# Sensor_PCB_M1.net
KiCad netlist of a schematic drawn in EAGLE
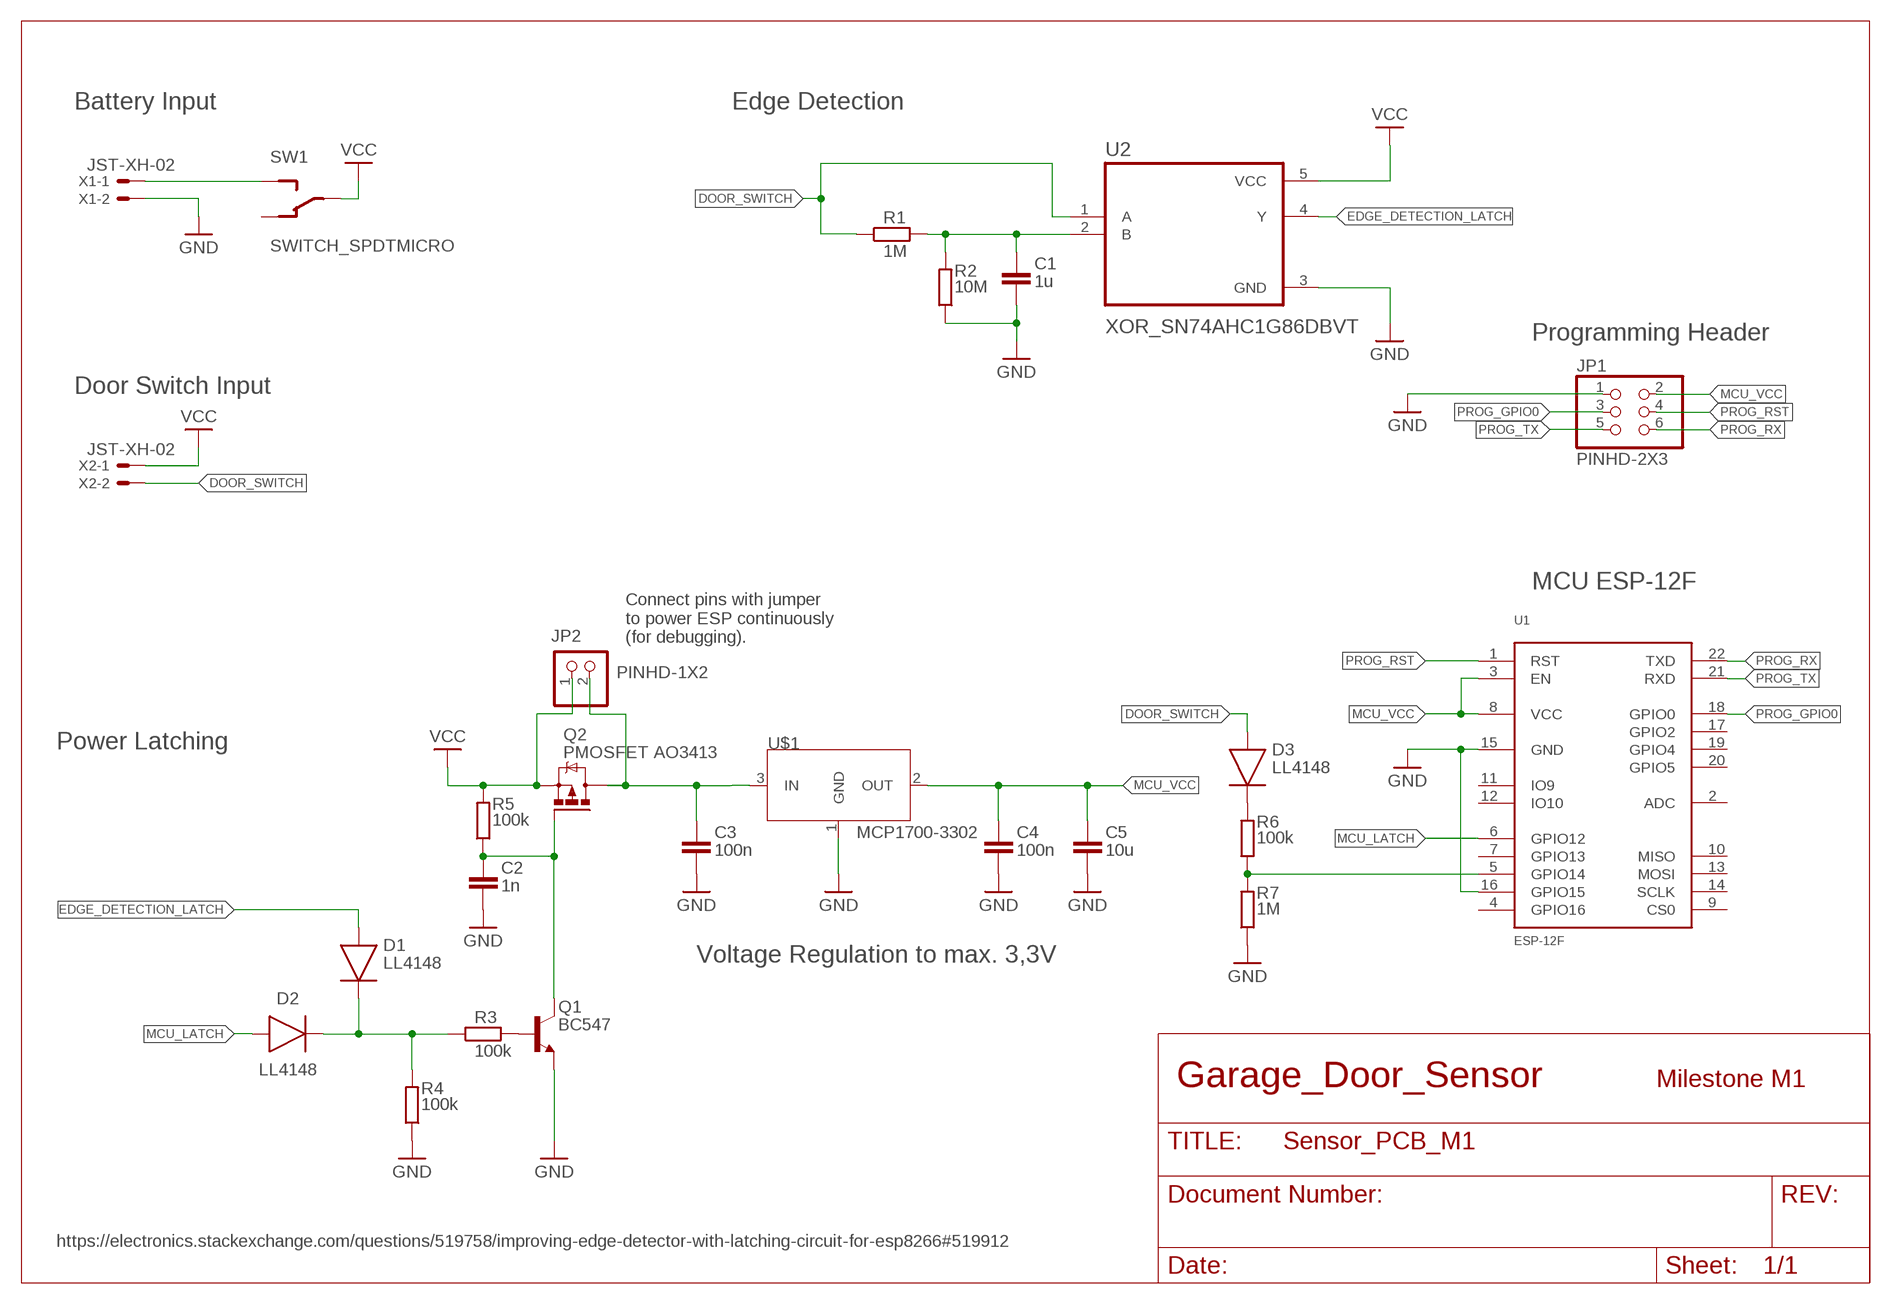
[diagram p0: schematic, sheet 1]

(export (version "E")
  (design (tool "Eeschema 10.0.6"))
  (components
    (comp (ref "C1")
      (value "1u")
      (footprint "eagle-import:CAPC2012X110")
      (libsource (lib "eagle-import") (part "CCHIP-0805(2012-METRIC)_"))
    )
    (comp (ref "C2")
      (value "1n")
      (footprint "eagle-import:CAPC2012X110")
      (libsource (lib "eagle-import") (part "CCHIP-0805(2012-METRIC)_"))
    )
    (comp (ref "C3")
      (value "100n")
      (footprint "eagle-import:CAPC2012X110")
      (libsource (lib "eagle-import") (part "CCHIP-0805(2012-METRIC)_"))
    )
    (comp (ref "C4")
      (value "100n")
      (footprint "eagle-import:CAPC2012X110")
      (libsource (lib "eagle-import") (part "CCHIP-0805(2012-METRIC)_"))
    )
    (comp (ref "C5")
      (value "10u")
      (footprint "eagle-import:CAPC2012X110")
      (libsource (lib "eagle-import") (part "CCHIP-0805(2012-METRIC)_"))
    )
    (comp (ref "D1")
      (value "LL4148")
      (footprint "eagle-import:DIOMELF3516")
      (fields (field (name "MANUFACTURER") "ON Semiconductor "))
      (libsource (lib "eagle-import") (part "DIODE__SOD-80LL4148"))
    )
    (comp (ref "D2")
      (value "LL4148")
      (footprint "eagle-import:DIOMELF3516")
      (fields (field (name "MANUFACTURER") "ON Semiconductor "))
      (libsource (lib "eagle-import") (part "DIODE__SOD-80LL4148"))
    )
    (comp (ref "D3")
      (value "LL4148")
      (footprint "eagle-import:DIOMELF3516")
      (fields (field (name "MANUFACTURER") "ON Semiconductor "))
      (libsource (lib "eagle-import") (part "DIODE__SOD-80LL4148"))
    )
    (comp (ref "JP1")
      (value "PINHD-2X3")
      (footprint "eagle-import:2X03")
      (fields (field (name "MANUFACTURER") "Generic"))
      (libsource (lib "eagle-import") (part "PINHD-2X3"))
    )
    (comp (ref "JP2")
      (value "PINHD-1X2")
      (footprint "eagle-import:1X02")
      (fields (field (name "MANUFACTURER") "Generic"))
      (libsource (lib "eagle-import") (part "PINHD-1X2"))
    )
    (comp (ref "Q1")
      (value "BC547")
      (footprint "eagle-import:SOT95P237X112-3N")
      (libsource (lib "eagle-import") (part "NPNSOT23-BEC_"))
    )
    (comp (ref "Q2")
      (value "PMOSFET AO3413")
      (footprint "eagle-import:SOT23")
      (libsource (lib "eagle-import") (part "PMOSFETSOT23-GSD_"))
    )
    (comp (ref "R1")
      (value "1M")
      (footprint "eagle-import:R0805")
      (libsource (lib "eagle-import") (part "R-EU_R0805"))
    )
    (comp (ref "R2")
      (value "10M")
      (footprint "eagle-import:R0805")
      (libsource (lib "eagle-import") (part "R-EU_R0805"))
    )
    (comp (ref "R3")
      (value "100k")
      (footprint "eagle-import:R0805")
      (libsource (lib "eagle-import") (part "R-EU_R0805"))
    )
    (comp (ref "R4")
      (value "100k")
      (footprint "eagle-import:R0805")
      (libsource (lib "eagle-import") (part "R-EU_R0805"))
    )
    (comp (ref "R5")
      (value "100k")
      (footprint "eagle-import:R0805")
      (libsource (lib "eagle-import") (part "R-EU_R0805"))
    )
    (comp (ref "R6")
      (value "100k")
      (footprint "eagle-import:R0805")
      (libsource (lib "eagle-import") (part "R-EU_R0805"))
    )
    (comp (ref "R7")
      (value "1M")
      (footprint "eagle-import:R0805")
      (libsource (lib "eagle-import") (part "R-EU_R0805"))
    )
    (comp (ref "SW1")
      (value "SWITCH_SPDTMICRO")
      (footprint "eagle-import:MICROSWITCH_SPDT")
      (libsource (lib "eagle-import") (part "SWITCH_SPDTMICRO"))
    )
    (comp (ref "U$1")
      (value "MCP1700-3302")
      (footprint "eagle-import:SOT23")
      (libsource (lib "eagle-import") (part "MCP1700-3302"))
    )
    (comp (ref "U1")
      (value "ESP-12F")
      (footprint "eagle-import:ESP-12F")
      (fields (field (name "MF") "AI-Thinker"))
      (libsource (lib "eagle-import") (part "ESP-12F"))
    )
    (comp (ref "U2")
      (value "XOR_SN74AHC1G86DBVT")
      (footprint "eagle-import:SOT95P280X145-5N")
      (fields (field (name "MF") "Texas Instruments") (field (name "MP") "SN74AHC1G86DBVT"))
      (libsource (lib "eagle-import") (part "SN74AHC1G86DBVT"))
    )
    (comp (ref "X1")
      (value "JST-XH-02")
      (footprint "eagle-import:JST-XH-02-PACKAGE-LONG-PAD")
      (libsource (lib "eagle-import") (part "JST-XH-02-PIN-LONG-PAD"))
    )
    (comp (ref "X2")
      (value "JST-XH-02")
      (footprint "eagle-import:JST-XH-02-PACKAGE-LONG-PAD")
      (libsource (lib "eagle-import") (part "JST-XH-02-PIN-LONG-PAD"))
    )
  )
  (nets
    (net (code "1") (name "DOOR_SWITCH") (class "Default")
      (node (ref "D3") (pin "2") (pinfunction "A_2") (pintype "passive"))
      (node (ref "R1") (pin "1") (pinfunction "1_1") (pintype "passive"))
      (node (ref "U2") (pin "1") (pinfunction "A_1") (pintype "input"))
      (node (ref "X2") (pin "2") (pinfunction "S_2") (pintype "passive"))
    )
    (net (code "2") (name "EDGE_DETECTION_LATCH") (class "Default")
      (node (ref "D1") (pin "2") (pinfunction "A_2") (pintype "passive"))
      (node (ref "U2") (pin "4") (pinfunction "Y_4") (pintype "output"))
    )
    (net (code "3") (name "GND") (class "Default")
      (node (ref "C1") (pin "2") (pinfunction "2_2") (pintype "passive"))
      (node (ref "C2") (pin "2") (pinfunction "2_2") (pintype "passive"))
      (node (ref "C3") (pin "2") (pinfunction "2_2") (pintype "passive"))
      (node (ref "C4") (pin "2") (pinfunction "2_2") (pintype "passive"))
      (node (ref "C5") (pin "2") (pinfunction "2_2") (pintype "passive"))
      (node (ref "JP1") (pin "1") (pinfunction "1_1") (pintype "passive"))
      (node (ref "Q1") (pin "2") (pinfunction "E_2") (pintype "passive"))
      (node (ref "R2") (pin "1") (pinfunction "1_1") (pintype "passive"))
      (node (ref "R4") (pin "1") (pinfunction "1_1") (pintype "passive"))
      (node (ref "R7") (pin "1") (pinfunction "1_1") (pintype "passive"))
      (node (ref "U$1") (pin "1") (pinfunction "GND_1") (pintype "bidirectional"))
      (node (ref "U1") (pin "15") (pinfunction "GND_15") (pintype "bidirectional"))
      (node (ref "U1") (pin "16") (pinfunction "GPIO15_16") (pintype "bidirectional"))
      (node (ref "U2") (pin "3") (pinfunction "GND_3") (pintype "power_in"))
      (node (ref "X1") (pin "2") (pinfunction "S_2") (pintype "passive"))
    )
    (net (code "4") (name "MCU_LATCH") (class "Default")
      (node (ref "D2") (pin "2") (pinfunction "A_2") (pintype "passive"))
      (node (ref "U1") (pin "6") (pinfunction "GPIO12_6") (pintype "bidirectional"))
    )
    (net (code "5") (name "MCU_VCC") (class "Default")
      (node (ref "C4") (pin "1") (pinfunction "1_1") (pintype "passive"))
      (node (ref "C5") (pin "1") (pinfunction "1_1") (pintype "passive"))
      (node (ref "JP1") (pin "2") (pinfunction "2_2") (pintype "passive"))
      (node (ref "U$1") (pin "2") (pinfunction "OUT_2") (pintype "bidirectional"))
      (node (ref "U1") (pin "3") (pinfunction "EN_3") (pintype "bidirectional"))
      (node (ref "U1") (pin "8") (pinfunction "VCC_8") (pintype "bidirectional"))
    )
    (net (code "6") (name "Net-(D1-C)") (class "Default")
      (node (ref "D1") (pin "1") (pinfunction "C_1") (pintype "passive"))
      (node (ref "D2") (pin "1") (pinfunction "C_1") (pintype "passive"))
      (node (ref "R3") (pin "1") (pinfunction "1_1") (pintype "passive"))
      (node (ref "R4") (pin "2") (pinfunction "2_2") (pintype "passive"))
    )
    (net (code "7") (name "Net-(D3-C)") (class "Default")
      (node (ref "D3") (pin "1") (pinfunction "C_1") (pintype "passive"))
      (node (ref "R6") (pin "2") (pinfunction "2_2") (pintype "passive"))
    )
    (net (code "8") (name "Net-(Q1-B)") (class "Default")
      (node (ref "Q1") (pin "1") (pinfunction "B_1") (pintype "passive"))
      (node (ref "R3") (pin "2") (pinfunction "2_2") (pintype "passive"))
    )
    (net (code "9") (name "Net-(Q1-C)") (class "Default")
      (node (ref "C2") (pin "1") (pinfunction "1_1") (pintype "passive"))
      (node (ref "Q1") (pin "3") (pinfunction "C_3") (pintype "passive"))
      (node (ref "Q2") (pin "1") (pinfunction "G_1") (pintype "passive"))
      (node (ref "R5") (pin "1") (pinfunction "1_1") (pintype "passive"))
    )
    (net (code "10") (name "Net-(Q2-D)") (class "Default")
      (node (ref "C3") (pin "1") (pinfunction "1_1") (pintype "passive"))
      (node (ref "JP2") (pin "2") (pinfunction "2_2") (pintype "passive"))
      (node (ref "Q2") (pin "3") (pinfunction "D_3") (pintype "passive"))
      (node (ref "U$1") (pin "3") (pinfunction "IN_3") (pintype "bidirectional"))
    )
    (net (code "11") (name "Net-(U1-GPIO14)") (class "Default")
      (node (ref "R6") (pin "1") (pinfunction "1_1") (pintype "passive"))
      (node (ref "R7") (pin "2") (pinfunction "2_2") (pintype "passive"))
      (node (ref "U1") (pin "5") (pinfunction "GPIO14_5") (pintype "bidirectional"))
    )
    (net (code "12") (name "Net-(U2-B)") (class "Default")
      (node (ref "C1") (pin "1") (pinfunction "1_1") (pintype "passive"))
      (node (ref "R1") (pin "2") (pinfunction "2_2") (pintype "passive"))
      (node (ref "R2") (pin "2") (pinfunction "2_2") (pintype "passive"))
      (node (ref "U2") (pin "2") (pinfunction "B_2") (pintype "input"))
    )
    (net (code "13") (name "Net-(X1A-S)") (class "Default")
      (node (ref "SW1") (pin "P$1") (pinfunction "P$1_P$1") (pintype "passive"))
      (node (ref "X1") (pin "1") (pinfunction "S_1") (pintype "passive"))
    )
    (net (code "14") (name "PROG_GPIO0") (class "Default")
      (node (ref "JP1") (pin "3") (pinfunction "3_3") (pintype "passive"))
      (node (ref "U1") (pin "18") (pinfunction "GPIO0_18") (pintype "bidirectional"))
    )
    (net (code "15") (name "PROG_RST") (class "Default")
      (node (ref "JP1") (pin "4") (pinfunction "4_4") (pintype "passive"))
      (node (ref "U1") (pin "1") (pinfunction "RST_1") (pintype "bidirectional"))
    )
    (net (code "16") (name "PROG_RX") (class "Default")
      (node (ref "JP1") (pin "6") (pinfunction "6_6") (pintype "passive"))
      (node (ref "U1") (pin "22") (pinfunction "TXD_22") (pintype "bidirectional"))
    )
    (net (code "17") (name "PROG_TX") (class "Default")
      (node (ref "JP1") (pin "5") (pinfunction "5_5") (pintype "passive"))
      (node (ref "U1") (pin "21") (pinfunction "RXD_21") (pintype "bidirectional"))
    )
    (net (code "18") (name "VCC") (class "Default")
      (node (ref "JP2") (pin "1") (pinfunction "1_1") (pintype "passive"))
      (node (ref "Q2") (pin "2") (pinfunction "S_2") (pintype "passive"))
      (node (ref "R5") (pin "2") (pinfunction "2_2") (pintype "passive"))
      (node (ref "SW1") (pin "P$2") (pinfunction "P$2_P$2") (pintype "passive"))
      (node (ref "U2") (pin "5") (pinfunction "VCC_5") (pintype "power_in"))
      (node (ref "X2") (pin "1") (pinfunction "S_1") (pintype "passive"))
    )
    (net (code "19") (name "unconnected-(SW1-PadP$3)") (class "Default")
      (node (ref "SW1") (pin "P$3") (pinfunction "P$3_P$3") (pintype "passive"))
    )
    (net (code "20") (name "unconnected-(U1-ADC-Pad2)") (class "Default")
      (node (ref "U1") (pin "2") (pinfunction "ADC_2") (pintype "bidirectional"))
    )
    (net (code "21") (name "unconnected-(U1-CS0-Pad9)") (class "Default")
      (node (ref "U1") (pin "9") (pinfunction "CS0_9") (pintype "bidirectional"))
    )
    (net (code "22") (name "unconnected-(U1-GPIO2-Pad17)") (class "Default")
      (node (ref "U1") (pin "17") (pinfunction "GPIO2_17") (pintype "bidirectional"))
    )
    (net (code "23") (name "unconnected-(U1-GPIO4-Pad19)") (class "Default")
      (node (ref "U1") (pin "19") (pinfunction "GPIO4_19") (pintype "bidirectional"))
    )
    (net (code "24") (name "unconnected-(U1-GPIO5-Pad20)") (class "Default")
      (node (ref "U1") (pin "20") (pinfunction "GPIO5_20") (pintype "bidirectional"))
    )
    (net (code "25") (name "unconnected-(U1-GPIO13-Pad7)") (class "Default")
      (node (ref "U1") (pin "7") (pinfunction "GPIO13_7") (pintype "bidirectional"))
    )
    (net (code "26") (name "unconnected-(U1-GPIO16-Pad4)") (class "Default")
      (node (ref "U1") (pin "4") (pinfunction "GPIO16_4") (pintype "bidirectional"))
    )
    (net (code "27") (name "unconnected-(U1-IO9-Pad11)") (class "Default")
      (node (ref "U1") (pin "11") (pinfunction "IO9_11") (pintype "bidirectional"))
    )
    (net (code "28") (name "unconnected-(U1-IO10-Pad12)") (class "Default")
      (node (ref "U1") (pin "12") (pinfunction "IO10_12") (pintype "bidirectional"))
    )
    (net (code "29") (name "unconnected-(U1-MISO-Pad10)") (class "Default")
      (node (ref "U1") (pin "10") (pinfunction "MISO_10") (pintype "bidirectional"))
    )
    (net (code "30") (name "unconnected-(U1-MOSI-Pad13)") (class "Default")
      (node (ref "U1") (pin "13") (pinfunction "MOSI_13") (pintype "bidirectional"))
    )
    (net (code "31") (name "unconnected-(U1-SCLK-Pad14)") (class "Default")
      (node (ref "U1") (pin "14") (pinfunction "SCLK_14") (pintype "bidirectional"))
    )
  )
)
